# voltage-sensor.net
KiCad netlist of a schematic drawn in EAGLE
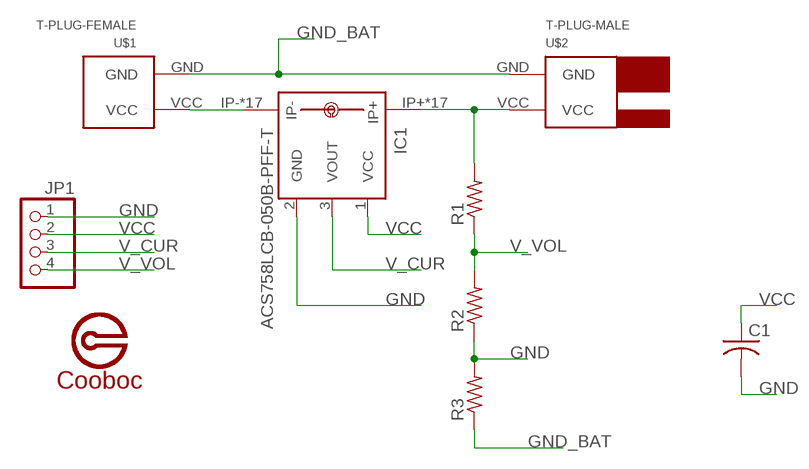
[diagram p0: schematic, sheet 1]

(export (version "E")
  (design (tool "Eeschema 10.0.6"))
  (components
    (comp (ref "C1")
      (value "C-USC0805K")
      (footprint "eagle-import:C0805K")
      (libsource (lib "eagle-import") (part "C-USC0805K"))
    )
    (comp (ref "IC1")
      (value "ACS758LCB-050B-PFF-T")
      (footprint "eagle-import:CB-PFF")
      (libsource (lib "eagle-import") (part "ACS758LCB-050B-PFF-T"))
    )
    (comp (ref "JP1")
      (value "PINHD-1X4")
      (footprint "eagle-import:1X04")
      (libsource (lib "eagle-import") (part "PINHD-1X4"))
    )
    (comp (ref "R1")
      (value "R-US_M0805")
      (footprint "eagle-import:M0805")
      (libsource (lib "eagle-import") (part "R-US_M0805"))
    )
    (comp (ref "R2")
      (value "R-US_M0805")
      (footprint "eagle-import:M0805")
      (libsource (lib "eagle-import") (part "R-US_M0805"))
    )
    (comp (ref "R3")
      (value "R-US_0207/10")
      (footprint "eagle-import:0207_10")
      (libsource (lib "eagle-import") (part "R-US_0207/10"))
    )
    (comp (ref "U$1")
      (value "T-PLUG-FEMALE")
      (footprint "eagle-import:T-FEMALE")
      (libsource (lib "eagle-import") (part "T-PLUG-FEMALE"))
    )
    (comp (ref "U$2")
      (value "T-PLUG-MALE")
      (footprint "eagle-import:T-MALE")
      (libsource (lib "eagle-import") (part "T-PLUG-MALE"))
    )
    (comp (ref "U$3")
      (value "COOBOC")
      (footprint "eagle-import:COOBOC")
      (libsource (lib "eagle-import") (part "COOBOC"))
    )
  )
  (nets
    (net (code "1") (name "/GND") (class "Default")
      (node (ref "C1") (pin "2") (pinfunction "2_2") (pintype "passive"))
      (node (ref "IC1") (pin "2") (pinfunction "GND_2") (pintype "power_in"))
      (node (ref "JP1") (pin "1") (pinfunction "1_1") (pintype "passive"))
      (node (ref "R2") (pin "1") (pinfunction "1_1") (pintype "passive"))
      (node (ref "R3") (pin "2") (pinfunction "2_2") (pintype "passive"))
    )
    (net (code "2") (name "/GND_BAT") (class "Default")
      (node (ref "R3") (pin "1") (pinfunction "1_1") (pintype "passive"))
      (node (ref "U$1") (pin "GND") (pinfunction "GND_GND") (pintype "bidirectional"))
      (node (ref "U$2") (pin "GND") (pinfunction "GND_GND") (pintype "bidirectional"))
    )
    (net (code "3") (name "/VCC") (class "Default")
      (node (ref "C1") (pin "1") (pinfunction "1_1") (pintype "passive"))
      (node (ref "IC1") (pin "1") (pinfunction "VCC_1") (pintype "power_in"))
      (node (ref "JP1") (pin "2") (pinfunction "2_2") (pintype "passive"))
    )
    (net (code "4") (name "/V_CUR") (class "Default")
      (node (ref "IC1") (pin "3") (pinfunction "VOUT_3") (pintype "output"))
      (node (ref "JP1") (pin "3") (pinfunction "3_3") (pintype "passive"))
    )
    (net (code "5") (name "/V_VOL") (class "Default")
      (node (ref "JP1") (pin "4") (pinfunction "4_4") (pintype "passive"))
      (node (ref "R1") (pin "1") (pinfunction "1_1") (pintype "passive"))
      (node (ref "R2") (pin "2") (pinfunction "2_2") (pintype "passive"))
    )
    (net (code "6") (name "Net-(IC1-IP+-PadIP+@10)") (class "Default")
      (node (ref "IC1") (pin "IP+") (pinfunction "IP+_IP+") (pintype "passive"))
      (node (ref "IC1") (pin "IP+@10") (pinfunction "IP+_IP+@10") (pintype "passive"))
      (node (ref "IC1") (pin "IP+@11") (pinfunction "IP+_IP+@11") (pintype "passive"))
      (node (ref "IC1") (pin "IP+@12") (pinfunction "IP+_IP+@12") (pintype "passive"))
      (node (ref "IC1") (pin "IP+@13") (pinfunction "IP+_IP+@13") (pintype "passive"))
      (node (ref "IC1") (pin "IP+@14") (pinfunction "IP+_IP+@14") (pintype "passive"))
      (node (ref "IC1") (pin "IP+@15") (pinfunction "IP+_IP+@15") (pintype "passive"))
      (node (ref "IC1") (pin "IP+@16") (pinfunction "IP+_IP+@16") (pintype "passive"))
      (node (ref "IC1") (pin "IP+@17") (pinfunction "IP+_IP+@17") (pintype "passive"))
      (node (ref "IC1") (pin "IP+@2") (pinfunction "IP+_IP+@2") (pintype "passive"))
      (node (ref "IC1") (pin "IP+@3") (pinfunction "IP+_IP+@3") (pintype "passive"))
      (node (ref "IC1") (pin "IP+@4") (pinfunction "IP+_IP+@4") (pintype "passive"))
      (node (ref "IC1") (pin "IP+@5") (pinfunction "IP+_IP+@5") (pintype "passive"))
      (node (ref "IC1") (pin "IP+@6") (pinfunction "IP+_IP+@6") (pintype "passive"))
      (node (ref "IC1") (pin "IP+@7") (pinfunction "IP+_IP+@7") (pintype "passive"))
      (node (ref "IC1") (pin "IP+@8") (pinfunction "IP+_IP+@8") (pintype "passive"))
      (node (ref "IC1") (pin "IP+@9") (pinfunction "IP+_IP+@9") (pintype "passive"))
      (node (ref "R1") (pin "2") (pinfunction "2_2") (pintype "passive"))
      (node (ref "U$2") (pin "VCC") (pinfunction "VCC_VCC") (pintype "bidirectional"))
    )
    (net (code "7") (name "Net-(IC1-IP--PadIP-@10)") (class "Default")
      (node (ref "IC1") (pin "IP-") (pinfunction "IP-_IP-") (pintype "passive"))
      (node (ref "IC1") (pin "IP-@10") (pinfunction "IP-_IP-@10") (pintype "passive"))
      (node (ref "IC1") (pin "IP-@11") (pinfunction "IP-_IP-@11") (pintype "passive"))
      (node (ref "IC1") (pin "IP-@12") (pinfunction "IP-_IP-@12") (pintype "passive"))
      (node (ref "IC1") (pin "IP-@13") (pinfunction "IP-_IP-@13") (pintype "passive"))
      (node (ref "IC1") (pin "IP-@14") (pinfunction "IP-_IP-@14") (pintype "passive"))
      (node (ref "IC1") (pin "IP-@15") (pinfunction "IP-_IP-@15") (pintype "passive"))
      (node (ref "IC1") (pin "IP-@16") (pinfunction "IP-_IP-@16") (pintype "passive"))
      (node (ref "IC1") (pin "IP-@17") (pinfunction "IP-_IP-@17") (pintype "passive"))
      (node (ref "IC1") (pin "IP-@2") (pinfunction "IP-_IP-@2") (pintype "passive"))
      (node (ref "IC1") (pin "IP-@3") (pinfunction "IP-_IP-@3") (pintype "passive"))
      (node (ref "IC1") (pin "IP-@4") (pinfunction "IP-_IP-@4") (pintype "passive"))
      (node (ref "IC1") (pin "IP-@5") (pinfunction "IP-_IP-@5") (pintype "passive"))
      (node (ref "IC1") (pin "IP-@6") (pinfunction "IP-_IP-@6") (pintype "passive"))
      (node (ref "IC1") (pin "IP-@7") (pinfunction "IP-_IP-@7") (pintype "passive"))
      (node (ref "IC1") (pin "IP-@8") (pinfunction "IP-_IP-@8") (pintype "passive"))
      (node (ref "IC1") (pin "IP-@9") (pinfunction "IP-_IP-@9") (pintype "passive"))
      (node (ref "U$1") (pin "VCC") (pinfunction "VCC_VCC") (pintype "bidirectional"))
    )
  )
)
